# Connectors.net
KiCad netlist of a schematic drawn in Altium Designer
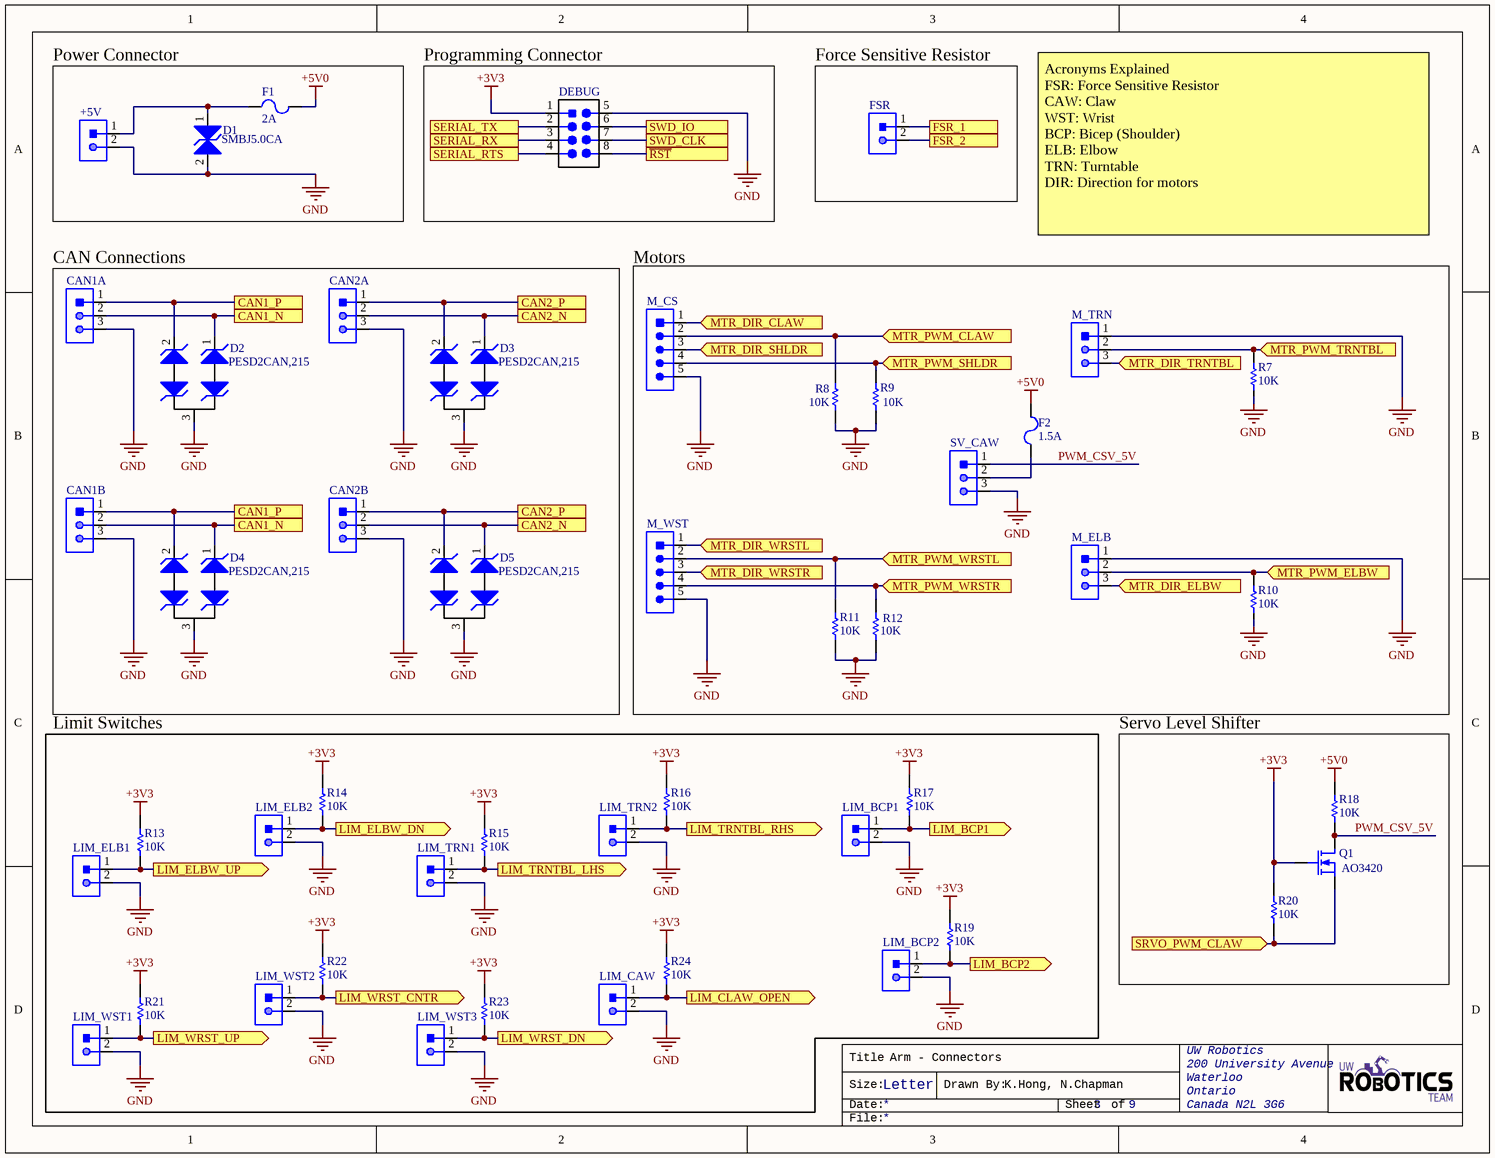
[diagram p0: Connectors.SchDoc]

(export (version "E")
  (design (tool "Eeschema 10.0.6"))
  (components
    (comp (ref "+5V")
      (value "CON_2M_SM4")
      (footprint "JST-B2B-SM4-TB")
      (description "CONN HEADER SMD 2POS 2MM")
      (fields
        (field (name "MANUFACTURER") "JST")
        (field (name "MANUFACTURER PART NUMBER") "B2B-PH-SM4-TB(LF)(SN)")
      )
      (libsource (lib "UWRT_Schematic_Library_2020") (part "CON_2M_SM4"))
    )
    (comp (ref "CAN1A")
      (value "CON_3M_SM4")
      (footprint "JST-B3B-SM4-TB")
      (description "CONN HEADER SMD 3POS 2MM")
      (fields
        (field (name "MANUFACTURER") "JST")
        (field (name "MANUFACTURER PART NUMBER") "B3B-PH-SM4-TB(LF)(SN)")
      )
      (libsource (lib "UWRT_Schematic_Library_2020") (part "CON_3M_SM4"))
    )
    (comp (ref "CAN1B")
      (value "CON_3M_SM4")
      (footprint "JST-B3B-SM4-TB")
      (description "CONN HEADER SMD 3POS 2MM")
      (fields
        (field (name "MANUFACTURER") "JST")
        (field (name "MANUFACTURER PART NUMBER") "B3B-PH-SM4-TB(LF)(SN)")
      )
      (libsource (lib "UWRT_Schematic_Library_2020") (part "CON_3M_SM4"))
    )
    (comp (ref "CAN2A")
      (value "CON_3M_SM4")
      (footprint "JST-B3B-SM4-TB")
      (description "CONN HEADER SMD 3POS 2MM")
      (fields
        (field (name "MANUFACTURER") "JST")
        (field (name "MANUFACTURER PART NUMBER") "B3B-PH-SM4-TB(LF)(SN)")
      )
      (libsource (lib "UWRT_Schematic_Library_2020") (part "CON_3M_SM4"))
    )
    (comp (ref "CAN2B")
      (value "CON_3M_SM4")
      (footprint "JST-B3B-SM4-TB")
      (description "CONN HEADER SMD 3POS 2MM")
      (fields
        (field (name "MANUFACTURER") "JST")
        (field (name "MANUFACTURER PART NUMBER") "B3B-PH-SM4-TB(LF)(SN)")
      )
      (libsource (lib "UWRT_Schematic_Library_2020") (part "CON_3M_SM4"))
    )
    (comp (ref "D1")
      (value "TVS_DIODE_BIDIRECTIONAL")
      (footprint "TVS_DIODE_BIDIRECTIONAL")
      (description "TVS DIODE 5V 9.2V DO214AA")
      (fields (field (name "MANUFACTURER PART NUMBER 1") "SMBJ5.0CA"))
      (libsource (lib "UWRT_Schematic_Library_2020") (part "TVS_DIODE_BIDIRECTIONAL"))
    )
    (comp (ref "D2")
      (value "TVS_DIODE_CAN")
      (footprint "NXP-SOT323-3")
      (description "TVS DIODE 24V 41V SOT323-3")
      (fields
        (field (name "MANUFACTURER") "Nexperia USA Inc.")
        (field (name "MANUFACTURER PART NUMBER") "PESD2CAN,215")
      )
      (libsource (lib "UWRT_Schematic_Library_2020") (part "TVS_DIODE_CAN"))
    )
    (comp (ref "D3")
      (value "TVS_DIODE_CAN")
      (footprint "NXP-SOT323-3")
      (description "TVS DIODE 24V 41V SOT323-3")
      (fields
        (field (name "MANUFACTURER") "Nexperia USA Inc.")
        (field (name "MANUFACTURER PART NUMBER") "PESD2CAN,215")
      )
      (libsource (lib "UWRT_Schematic_Library_2020") (part "TVS_DIODE_CAN"))
    )
    (comp (ref "D4")
      (value "TVS_DIODE_CAN")
      (footprint "NXP-SOT323-3")
      (description "TVS DIODE 24V 41V SOT323-3")
      (fields
        (field (name "MANUFACTURER") "Nexperia USA Inc.")
        (field (name "MANUFACTURER PART NUMBER") "PESD2CAN,215")
      )
      (libsource (lib "UWRT_Schematic_Library_2020") (part "TVS_DIODE_CAN"))
    )
    (comp (ref "D5")
      (value "TVS_DIODE_CAN")
      (footprint "NXP-SOT323-3")
      (description "TVS DIODE 24V 41V SOT323-3")
      (fields
        (field (name "MANUFACTURER") "Nexperia USA Inc.")
        (field (name "MANUFACTURER PART NUMBER") "PESD2CAN,215")
      )
      (libsource (lib "UWRT_Schematic_Library_2020") (part "TVS_DIODE_CAN"))
    )
    (comp (ref "DEBUG")
      (value "HEADER 4X2")
      (footprint "HEADER_2X4")
      (description "CONN HEADER VERT 8POS 2.54MM")
      (libsource (lib "UWRT_Schematic_Library_2020") (part "HEADER 4X2"))
    )
    (comp (ref "F1")
      (value "FUSE_2A_0603")
      (footprint "FUSE_0603")
      (description "FUSE SMD 2A 32V")
      (fields (field (name "CURRENT RATING") "2A"))
      (libsource (lib "UWRT_Schematic_Library_2020") (part "FUSE_2A_0603"))
    )
    (comp (ref "F2")
      (value "FUSE_1.5A_0603")
      (footprint "FUSE_0603")
      (description "FUSE SMD 1.5A 32V")
      (fields (field (name "CURRENT RATING") "1.5A"))
      (libsource (lib "UWRT_Schematic_Library_2020") (part "FUSE_1.5A_0603"))
    )
    (comp (ref "FSR")
      (value "CON_2M_SM4")
      (footprint "JST-B2B-SM4-TB")
      (description "CONN HEADER SMD 2POS 2MM")
      (fields
        (field (name "MANUFACTURER") "JST")
        (field (name "MANUFACTURER PART NUMBER") "B2B-PH-SM4-TB(LF)(SN)")
      )
      (libsource (lib "UWRT_Schematic_Library_2020") (part "CON_2M_SM4"))
    )
    (comp (ref "LIM_BCP1")
      (value "CON_2M_SM4")
      (footprint "JST-B2B-SM4-TB")
      (description "CONN HEADER SMD 2POS 2MM")
      (fields
        (field (name "MANUFACTURER") "JST")
        (field (name "MANUFACTURER PART NUMBER") "B2B-PH-SM4-TB(LF)(SN)")
      )
      (libsource (lib "UWRT_Schematic_Library_2020") (part "CON_2M_SM4"))
    )
    (comp (ref "LIM_BCP2")
      (value "CON_2M_SM4")
      (footprint "JST-B2B-SM4-TB")
      (description "CONN HEADER SMD 2POS 2MM")
      (fields
        (field (name "MANUFACTURER") "JST")
        (field (name "MANUFACTURER PART NUMBER") "B2B-PH-SM4-TB(LF)(SN)")
      )
      (libsource (lib "UWRT_Schematic_Library_2020") (part "CON_2M_SM4"))
    )
    (comp (ref "LIM_CAW")
      (value "CON_2M_SM4")
      (footprint "JST-B2B-SM4-TB")
      (description "CONN HEADER SMD 2POS 2MM")
      (fields
        (field (name "MANUFACTURER") "JST")
        (field (name "MANUFACTURER PART NUMBER") "B2B-PH-SM4-TB(LF)(SN)")
      )
      (libsource (lib "UWRT_Schematic_Library_2020") (part "CON_2M_SM4"))
    )
    (comp (ref "LIM_ELB1")
      (value "CON_2M_SM4")
      (footprint "JST-B2B-SM4-TB")
      (description "CONN HEADER SMD 2POS 2MM")
      (fields
        (field (name "MANUFACTURER") "JST")
        (field (name "MANUFACTURER PART NUMBER") "B2B-PH-SM4-TB(LF)(SN)")
      )
      (libsource (lib "UWRT_Schematic_Library_2020") (part "CON_2M_SM4"))
    )
    (comp (ref "LIM_ELB2")
      (value "CON_2M_SM4")
      (footprint "JST-B2B-SM4-TB")
      (description "CONN HEADER SMD 2POS 2MM")
      (fields
        (field (name "MANUFACTURER") "JST")
        (field (name "MANUFACTURER PART NUMBER") "B2B-PH-SM4-TB(LF)(SN)")
      )
      (libsource (lib "UWRT_Schematic_Library_2020") (part "CON_2M_SM4"))
    )
    (comp (ref "LIM_TRN1")
      (value "CON_2M_SM4")
      (footprint "JST-B2B-SM4-TB")
      (description "CONN HEADER SMD 2POS 2MM")
      (fields
        (field (name "MANUFACTURER") "JST")
        (field (name "MANUFACTURER PART NUMBER") "B2B-PH-SM4-TB(LF)(SN)")
      )
      (libsource (lib "UWRT_Schematic_Library_2020") (part "CON_2M_SM4"))
    )
    (comp (ref "LIM_TRN2")
      (value "CON_2M_SM4")
      (footprint "JST-B2B-SM4-TB")
      (description "CONN HEADER SMD 2POS 2MM")
      (fields
        (field (name "MANUFACTURER") "JST")
        (field (name "MANUFACTURER PART NUMBER") "B2B-PH-SM4-TB(LF)(SN)")
      )
      (libsource (lib "UWRT_Schematic_Library_2020") (part "CON_2M_SM4"))
    )
    (comp (ref "LIM_WST1")
      (value "CON_2M_SM4")
      (footprint "JST-B2B-SM4-TB")
      (description "CONN HEADER SMD 2POS 2MM")
      (fields
        (field (name "MANUFACTURER") "JST")
        (field (name "MANUFACTURER PART NUMBER") "B2B-PH-SM4-TB(LF)(SN)")
      )
      (libsource (lib "UWRT_Schematic_Library_2020") (part "CON_2M_SM4"))
    )
    (comp (ref "LIM_WST2")
      (value "CON_2M_SM4")
      (footprint "JST-B2B-SM4-TB")
      (description "CONN HEADER SMD 2POS 2MM")
      (fields
        (field (name "MANUFACTURER") "JST")
        (field (name "MANUFACTURER PART NUMBER") "B2B-PH-SM4-TB(LF)(SN)")
      )
      (libsource (lib "UWRT_Schematic_Library_2020") (part "CON_2M_SM4"))
    )
    (comp (ref "LIM_WST3")
      (value "CON_2M_SM4")
      (footprint "JST-B2B-SM4-TB")
      (description "CONN HEADER SMD 2POS 2MM")
      (fields
        (field (name "MANUFACTURER") "JST")
        (field (name "MANUFACTURER PART NUMBER") "B2B-PH-SM4-TB(LF)(SN)")
      )
      (libsource (lib "UWRT_Schematic_Library_2020") (part "CON_2M_SM4"))
    )
    (comp (ref "M_CS")
      (value "CON_5M_SM4")
      (footprint "JST-B5B-SM4-TB")
      (description "CONN HEADER SMD 5POS 2MM")
      (fields
        (field (name "MANUFACTURER") "JST")
        (field (name "MANUFACTURER PART NUMBER") "B5B-PH-SM4-TB(LF)(SN)")
      )
      (libsource (lib "UWRT_Schematic_Library_2020") (part "CON_5M_SM4"))
    )
    (comp (ref "M_ELB")
      (value "CON_3M_SM4")
      (footprint "JST-B3B-SM4-TB")
      (description "CONN HEADER SMD 3POS 2MM")
      (fields
        (field (name "MANUFACTURER") "JST")
        (field (name "MANUFACTURER PART NUMBER") "B3B-PH-SM4-TB(LF)(SN)")
      )
      (libsource (lib "UWRT_Schematic_Library_2020") (part "CON_3M_SM4"))
    )
    (comp (ref "M_TRN")
      (value "CON_3M_SM4")
      (footprint "JST-B3B-SM4-TB")
      (description "CONN HEADER SMD 3POS 2MM")
      (fields
        (field (name "MANUFACTURER") "JST")
        (field (name "MANUFACTURER PART NUMBER") "B3B-PH-SM4-TB(LF)(SN)")
      )
      (libsource (lib "UWRT_Schematic_Library_2020") (part "CON_3M_SM4"))
    )
    (comp (ref "M_WST")
      (value "CON_5M_SM4")
      (footprint "JST-B5B-SM4-TB")
      (description "CONN HEADER SMD 5POS 2MM")
      (fields
        (field (name "MANUFACTURER") "JST")
        (field (name "MANUFACTURER PART NUMBER") "B5B-PH-SM4-TB(LF)(SN)")
      )
      (libsource (lib "UWRT_Schematic_Library_2020") (part "CON_5M_SM4"))
    )
    (comp (ref "Q1")
      (value "NMOS_20V_6A")
      (footprint "NMOS_SOT23-3")
      (description "MOSFET N-CH 20V 6A SOT23")
      (fields (field (name "MPN") "AO3420") (field (name "MANUFACTURER") "Alpha & Omega"))
      (libsource (lib "UWRT_Schematic_Library_2020") (part "NMOS_20V_6A"))
    )
    (comp (ref "R7")
      (value "10K")
      (footprint "RESC0603(1608)_N")
      (description "RES SMD 10K OHM 5% 1/10W 0603")
      (fields (field (name "MANUFACTURER") "Yageo") (field (name "MPN") "RC0603JR-0710KL"))
      (libsource (lib "UWRT_Schematic_Library_2020") (part "RES_10K_0603"))
    )
    (comp (ref "R8")
      (value "10K")
      (footprint "RESC0603(1608)_N")
      (description "RES SMD 10K OHM 5% 1/10W 0603")
      (fields (field (name "MANUFACTURER") "Yageo") (field (name "MPN") "RC0603JR-0710KL"))
      (libsource (lib "UWRT_Schematic_Library_2020") (part "RES_10K_0603"))
    )
    (comp (ref "R9")
      (value "10K")
      (footprint "RESC0603(1608)_N")
      (description "RES SMD 10K OHM 5% 1/10W 0603")
      (fields (field (name "MANUFACTURER") "Yageo") (field (name "MPN") "RC0603JR-0710KL"))
      (libsource (lib "UWRT_Schematic_Library_2020") (part "RES_10K_0603"))
    )
    (comp (ref "R10")
      (value "10K")
      (footprint "RESC0603(1608)_N")
      (description "RES SMD 10K OHM 5% 1/10W 0603")
      (fields (field (name "MANUFACTURER") "Yageo") (field (name "MPN") "RC0603JR-0710KL"))
      (libsource (lib "UWRT_Schematic_Library_2020") (part "RES_10K_0603"))
    )
    (comp (ref "R11")
      (value "10K")
      (footprint "RESC0603(1608)_N")
      (description "RES SMD 10K OHM 5% 1/10W 0603")
      (fields (field (name "MANUFACTURER") "Yageo") (field (name "MPN") "RC0603JR-0710KL"))
      (libsource (lib "UWRT_Schematic_Library_2020") (part "RES_10K_0603"))
    )
    (comp (ref "R12")
      (value "10K")
      (footprint "RESC0603(1608)_N")
      (description "RES SMD 10K OHM 5% 1/10W 0603")
      (fields (field (name "MANUFACTURER") "Yageo") (field (name "MPN") "RC0603JR-0710KL"))
      (libsource (lib "UWRT_Schematic_Library_2020") (part "RES_10K_0603"))
    )
    (comp (ref "R13")
      (value "10K")
      (footprint "RESC0603(1608)_N")
      (description "RES SMD 10K OHM 5% 1/10W 0603")
      (fields (field (name "MANUFACTURER") "Yageo") (field (name "MPN") "RC0603JR-0710KL"))
      (libsource (lib "UWRT_Schematic_Library_2020") (part "RES_10K_0603"))
    )
    (comp (ref "R14")
      (value "10K")
      (footprint "RESC0603(1608)_N")
      (description "RES SMD 10K OHM 5% 1/10W 0603")
      (fields (field (name "MANUFACTURER") "Yageo") (field (name "MPN") "RC0603JR-0710KL"))
      (libsource (lib "UWRT_Schematic_Library_2020") (part "RES_10K_0603"))
    )
    (comp (ref "R15")
      (value "10K")
      (footprint "RESC0603(1608)_N")
      (description "RES SMD 10K OHM 5% 1/10W 0603")
      (fields (field (name "MANUFACTURER") "Yageo") (field (name "MPN") "RC0603JR-0710KL"))
      (libsource (lib "UWRT_Schematic_Library_2020") (part "RES_10K_0603"))
    )
    (comp (ref "R16")
      (value "10K")
      (footprint "RESC0603(1608)_N")
      (description "RES SMD 10K OHM 5% 1/10W 0603")
      (fields (field (name "MANUFACTURER") "Yageo") (field (name "MPN") "RC0603JR-0710KL"))
      (libsource (lib "UWRT_Schematic_Library_2020") (part "RES_10K_0603"))
    )
    (comp (ref "R17")
      (value "10K")
      (footprint "RESC0603(1608)_N")
      (description "RES SMD 10K OHM 5% 1/10W 0603")
      (fields (field (name "MANUFACTURER") "Yageo") (field (name "MPN") "RC0603JR-0710KL"))
      (libsource (lib "UWRT_Schematic_Library_2020") (part "RES_10K_0603"))
    )
    (comp (ref "R18")
      (value "10K")
      (footprint "RESC0603(1608)_N")
      (description "RES SMD 10K OHM 5% 1/10W 0603")
      (fields (field (name "MANUFACTURER") "Yageo") (field (name "MPN") "RC0603JR-0710KL"))
      (libsource (lib "UWRT_Schematic_Library_2020") (part "RES_10K_0603"))
    )
    (comp (ref "R19")
      (value "10K")
      (footprint "RESC0603(1608)_N")
      (description "RES SMD 10K OHM 5% 1/10W 0603")
      (fields (field (name "MANUFACTURER") "Yageo") (field (name "MPN") "RC0603JR-0710KL"))
      (libsource (lib "UWRT_Schematic_Library_2020") (part "RES_10K_0603"))
    )
    (comp (ref "R20")
      (value "10K")
      (footprint "RESC0603(1608)_N")
      (description "RES SMD 10K OHM 5% 1/10W 0603")
      (fields (field (name "MANUFACTURER") "Yageo") (field (name "MPN") "RC0603JR-0710KL"))
      (libsource (lib "UWRT_Schematic_Library_2020") (part "RES_10K_0603"))
    )
    (comp (ref "R21")
      (value "10K")
      (footprint "RESC0603(1608)_N")
      (description "RES SMD 10K OHM 5% 1/10W 0603")
      (fields (field (name "MANUFACTURER") "Yageo") (field (name "MPN") "RC0603JR-0710KL"))
      (libsource (lib "UWRT_Schematic_Library_2020") (part "RES_10K_0603"))
    )
    (comp (ref "R22")
      (value "10K")
      (footprint "RESC0603(1608)_N")
      (description "RES SMD 10K OHM 5% 1/10W 0603")
      (fields (field (name "MANUFACTURER") "Yageo") (field (name "MPN") "RC0603JR-0710KL"))
      (libsource (lib "UWRT_Schematic_Library_2020") (part "RES_10K_0603"))
    )
    (comp (ref "R23")
      (value "10K")
      (footprint "RESC0603(1608)_N")
      (description "RES SMD 10K OHM 5% 1/10W 0603")
      (fields (field (name "MANUFACTURER") "Yageo") (field (name "MPN") "RC0603JR-0710KL"))
      (libsource (lib "UWRT_Schematic_Library_2020") (part "RES_10K_0603"))
    )
    (comp (ref "R24")
      (value "10K")
      (footprint "RESC0603(1608)_N")
      (description "RES SMD 10K OHM 5% 1/10W 0603")
      (fields (field (name "MANUFACTURER") "Yageo") (field (name "MPN") "RC0603JR-0710KL"))
      (libsource (lib "UWRT_Schematic_Library_2020") (part "RES_10K_0603"))
    )
    (comp (ref "SV_CAW")
      (value "CON_3M_SM4")
      (footprint "JST-B3B-SM4-TB")
      (description "CONN HEADER SMD 3POS 2MM")
      (fields
        (field (name "MANUFACTURER") "JST")
        (field (name "MANUFACTURER PART NUMBER") "B3B-PH-SM4-TB(LF)(SN)")
      )
      (libsource (lib "UWRT_Schematic_Library_2020") (part "CON_3M_SM4"))
    )
  )
  (nets
    (net (code "1") (name "+3V3") (class "Default")
      (node (ref "DEBUG") (pin "1") (pinfunction "VCC_1") (pintype "passive"))
      (node (ref "Q1") (pin "1") (pinfunction "G_1") (pintype "passive"))
      (node (ref "R13") (pin "2") (pinfunction "2_2") (pintype "passive"))
      (node (ref "R14") (pin "2") (pinfunction "2_2") (pintype "passive"))
      (node (ref "R15") (pin "2") (pinfunction "2_2") (pintype "passive"))
      (node (ref "R16") (pin "2") (pinfunction "2_2") (pintype "passive"))
      (node (ref "R17") (pin "2") (pinfunction "2_2") (pintype "passive"))
      (node (ref "R19") (pin "2") (pinfunction "2_2") (pintype "passive"))
      (node (ref "R20") (pin "2") (pinfunction "2_2") (pintype "passive"))
      (node (ref "R21") (pin "2") (pinfunction "2_2") (pintype "passive"))
      (node (ref "R22") (pin "2") (pinfunction "2_2") (pintype "passive"))
      (node (ref "R23") (pin "2") (pinfunction "2_2") (pintype "passive"))
      (node (ref "R24") (pin "2") (pinfunction "2_2") (pintype "passive"))
    )
    (net (code "2") (name "+5V0") (class "Default")
      (node (ref "F1") (pin "2") (pinfunction "2_2") (pintype "passive"))
      (node (ref "F2") (pin "2") (pinfunction "2_2") (pintype "passive"))
      (node (ref "R18") (pin "2") (pinfunction "2_2") (pintype "passive"))
    )
    (net (code "3") (name "/CAN1_N") (class "Default")
      (node (ref "CAN1A") (pin "2") (pinfunction "2_2") (pintype "passive"))
      (node (ref "CAN1B") (pin "2") (pinfunction "2_2") (pintype "passive"))
      (node (ref "D2") (pin "1") (pinfunction "1_1") (pintype "passive"))
      (node (ref "D4") (pin "1") (pinfunction "1_1") (pintype "passive"))
    )
    (net (code "4") (name "/CAN1_P") (class "Default")
      (node (ref "CAN1A") (pin "1") (pinfunction "1_1") (pintype "passive"))
      (node (ref "CAN1B") (pin "1") (pinfunction "1_1") (pintype "passive"))
      (node (ref "D2") (pin "2") (pinfunction "2_2") (pintype "passive"))
      (node (ref "D4") (pin "2") (pinfunction "2_2") (pintype "passive"))
    )
    (net (code "5") (name "/CAN2_N") (class "Default")
      (node (ref "CAN2A") (pin "2") (pinfunction "2_2") (pintype "passive"))
      (node (ref "CAN2B") (pin "2") (pinfunction "2_2") (pintype "passive"))
      (node (ref "D3") (pin "1") (pinfunction "1_1") (pintype "passive"))
      (node (ref "D5") (pin "1") (pinfunction "1_1") (pintype "passive"))
    )
    (net (code "6") (name "/CAN2_P") (class "Default")
      (node (ref "CAN2A") (pin "1") (pinfunction "1_1") (pintype "passive"))
      (node (ref "CAN2B") (pin "1") (pinfunction "1_1") (pintype "passive"))
      (node (ref "D3") (pin "2") (pinfunction "2_2") (pintype "passive"))
      (node (ref "D5") (pin "2") (pinfunction "2_2") (pintype "passive"))
    )
    (net (code "7") (name "/FSR_1") (class "Default")
      (node (ref "FSR") (pin "1") (pinfunction "1_1") (pintype "passive"))
    )
    (net (code "8") (name "/FSR_2") (class "Default")
      (node (ref "FSR") (pin "2") (pinfunction "2_2") (pintype "passive"))
    )
    (net (code "9") (name "/LIM_BCP1") (class "Default")
      (node (ref "LIM_BCP1") (pin "1") (pinfunction "1_1") (pintype "passive"))
      (node (ref "R17") (pin "1") (pinfunction "1_1") (pintype "passive"))
    )
    (net (code "10") (name "/LIM_BCP2") (class "Default")
      (node (ref "LIM_BCP2") (pin "1") (pinfunction "1_1") (pintype "passive"))
      (node (ref "R19") (pin "1") (pinfunction "1_1") (pintype "passive"))
    )
    (net (code "11") (name "/LIM_CLAW_OPEN") (class "Default")
      (node (ref "LIM_CAW") (pin "1") (pinfunction "1_1") (pintype "passive"))
      (node (ref "R24") (pin "1") (pinfunction "1_1") (pintype "passive"))
    )
    (net (code "12") (name "/LIM_ELBW_DN") (class "Default")
      (node (ref "LIM_ELB2") (pin "1") (pinfunction "1_1") (pintype "passive"))
      (node (ref "R14") (pin "1") (pinfunction "1_1") (pintype "passive"))
    )
    (net (code "13") (name "/LIM_ELBW_UP") (class "Default")
      (node (ref "LIM_ELB1") (pin "1") (pinfunction "1_1") (pintype "passive"))
      (node (ref "R13") (pin "1") (pinfunction "1_1") (pintype "passive"))
    )
    (net (code "14") (name "/LIM_TRNTBL_LHS") (class "Default")
      (node (ref "LIM_TRN1") (pin "1") (pinfunction "1_1") (pintype "passive"))
      (node (ref "R15") (pin "1") (pinfunction "1_1") (pintype "passive"))
    )
    (net (code "15") (name "/LIM_TRNTBL_RHS") (class "Default")
      (node (ref "LIM_TRN2") (pin "1") (pinfunction "1_1") (pintype "passive"))
      (node (ref "R16") (pin "1") (pinfunction "1_1") (pintype "passive"))
    )
    (net (code "16") (name "/LIM_WRST_CNTR") (class "Default")
      (node (ref "LIM_WST2") (pin "1") (pinfunction "1_1") (pintype "passive"))
      (node (ref "R22") (pin "1") (pinfunction "1_1") (pintype "passive"))
    )
    (net (code "17") (name "/LIM_WRST_DN") (class "Default")
      (node (ref "LIM_WST3") (pin "1") (pinfunction "1_1") (pintype "passive"))
      (node (ref "R23") (pin "1") (pinfunction "1_1") (pintype "passive"))
    )
    (net (code "18") (name "/LIM_WRST_UP") (class "Default")
      (node (ref "LIM_WST1") (pin "1") (pinfunction "1_1") (pintype "passive"))
      (node (ref "R21") (pin "1") (pinfunction "1_1") (pintype "passive"))
    )
    (net (code "19") (name "/MTR_DIR_CLAW") (class "Default")
      (node (ref "M_CS") (pin "1") (pinfunction "1_1") (pintype "passive"))
    )
    (net (code "20") (name "/MTR_DIR_ELBW") (class "Default")
      (node (ref "M_ELB") (pin "3") (pinfunction "3_3") (pintype "passive"))
    )
    (net (code "21") (name "/MTR_DIR_SHLDR") (class "Default")
      (node (ref "M_CS") (pin "3") (pinfunction "3_3") (pintype "passive"))
    )
    (net (code "22") (name "/MTR_DIR_TRNTBL") (class "Default")
      (node (ref "M_TRN") (pin "3") (pinfunction "3_3") (pintype "passive"))
    )
    (net (code "23") (name "/MTR_DIR_WRSTL") (class "Default")
      (node (ref "M_WST") (pin "1") (pinfunction "1_1") (pintype "passive"))
    )
    (net (code "24") (name "/MTR_DIR_WRSTR") (class "Default")
      (node (ref "M_WST") (pin "3") (pinfunction "3_3") (pintype "passive"))
    )
    (net (code "25") (name "/MTR_PWM_CLAW") (class "Default")
      (node (ref "M_CS") (pin "2") (pinfunction "2_2") (pintype "passive"))
      (node (ref "R8") (pin "2") (pinfunction "2_2") (pintype "passive"))
    )
    (net (code "26") (name "/MTR_PWM_ELBW") (class "Default")
      (node (ref "M_ELB") (pin "2") (pinfunction "2_2") (pintype "passive"))
      (node (ref "R10") (pin "2") (pinfunction "2_2") (pintype "passive"))
    )
    (net (code "27") (name "/MTR_PWM_SHLDR") (class "Default")
      (node (ref "M_CS") (pin "4") (pinfunction "4_4") (pintype "passive"))
      (node (ref "R9") (pin "2") (pinfunction "2_2") (pintype "passive"))
    )
    (net (code "28") (name "/MTR_PWM_TRNTBL") (class "Default")
      (node (ref "M_TRN") (pin "2") (pinfunction "2_2") (pintype "passive"))
      (node (ref "R7") (pin "2") (pinfunction "2_2") (pintype "passive"))
    )
    (net (code "29") (name "/MTR_PWM_WRSTL") (class "Default")
      (node (ref "M_WST") (pin "2") (pinfunction "2_2") (pintype "passive"))
      (node (ref "R11") (pin "2") (pinfunction "2_2") (pintype "passive"))
    )
    (net (code "30") (name "/MTR_PWM_WRSTR") (class "Default")
      (node (ref "M_WST") (pin "4") (pinfunction "4_4") (pintype "passive"))
      (node (ref "R12") (pin "2") (pinfunction "2_2") (pintype "passive"))
    )
    (net (code "31") (name "/PWM_CSV_5V") (class "Default")
      (node (ref "Q1") (pin "3") (pinfunction "D_3") (pintype "passive"))
      (node (ref "R18") (pin "1") (pinfunction "1_1") (pintype "passive"))
      (node (ref "SV_CAW") (pin "1") (pinfunction "1_1") (pintype "passive"))
    )
    (net (code "32") (name "/SERIAL_RTS") (class "Default")
      (node (ref "DEBUG") (pin "4") (pinfunction "4_4") (pintype "passive"))
    )
    (net (code "33") (name "/SERIAL_RX") (class "Default")
      (node (ref "DEBUG") (pin "3") (pinfunction "3_3") (pintype "passive"))
    )
    (net (code "34") (name "/SERIAL_TX") (class "Default")
      (node (ref "DEBUG") (pin "2") (pinfunction "2_2") (pintype "passive"))
    )
    (net (code "35") (name "/SRVO_PWM_CLAW") (class "Default")
      (node (ref "Q1") (pin "2") (pinfunction "S_2") (pintype "passive"))
      (node (ref "R20") (pin "1") (pinfunction "1_1") (pintype "passive"))
    )
    (net (code "36") (name "/SWD_CLK") (class "Default")
      (node (ref "DEBUG") (pin "7") (pinfunction "3_7") (pintype "passive"))
    )
    (net (code "37") (name "/SWD_IO") (class "Default")
      (node (ref "DEBUG") (pin "6") (pinfunction "2_6") (pintype "passive"))
    )
    (net (code "38") (name "/~{RST}") (class "Default")
      (node (ref "DEBUG") (pin "8") (pinfunction "4_8") (pintype "passive"))
    )
    (net (code "39") (name "GND") (class "Default")
      (node (ref "+5V") (pin "2") (pinfunction "2_2") (pintype "passive"))
      (node (ref "CAN1A") (pin "3") (pinfunction "3_3") (pintype "passive"))
      (node (ref "CAN1B") (pin "3") (pinfunction "3_3") (pintype "passive"))
      (node (ref "CAN2A") (pin "3") (pinfunction "3_3") (pintype "passive"))
      (node (ref "CAN2B") (pin "3") (pinfunction "3_3") (pintype "passive"))
      (node (ref "D1") (pin "2") (pinfunction "2_2") (pintype "passive"))
      (node (ref "D2") (pin "3") (pinfunction "3_3") (pintype "passive"))
      (node (ref "D3") (pin "3") (pinfunction "3_3") (pintype "passive"))
      (node (ref "D4") (pin "3") (pinfunction "3_3") (pintype "passive"))
      (node (ref "D5") (pin "3") (pinfunction "3_3") (pintype "passive"))
      (node (ref "DEBUG") (pin "5") (pinfunction "GND_5") (pintype "passive"))
      (node (ref "LIM_BCP1") (pin "2") (pinfunction "2_2") (pintype "passive"))
      (node (ref "LIM_BCP2") (pin "2") (pinfunction "2_2") (pintype "passive"))
      (node (ref "LIM_CAW") (pin "2") (pinfunction "2_2") (pintype "passive"))
      (node (ref "LIM_ELB1") (pin "2") (pinfunction "2_2") (pintype "passive"))
      (node (ref "LIM_ELB2") (pin "2") (pinfunction "2_2") (pintype "passive"))
      (node (ref "LIM_TRN1") (pin "2") (pinfunction "2_2") (pintype "passive"))
      (node (ref "LIM_TRN2") (pin "2") (pinfunction "2_2") (pintype "passive"))
      (node (ref "LIM_WST1") (pin "2") (pinfunction "2_2") (pintype "passive"))
      (node (ref "LIM_WST2") (pin "2") (pinfunction "2_2") (pintype "passive"))
      (node (ref "LIM_WST3") (pin "2") (pinfunction "2_2") (pintype "passive"))
      (node (ref "M_CS") (pin "5") (pinfunction "5_5") (pintype "passive"))
      (node (ref "M_ELB") (pin "1") (pinfunction "1_1") (pintype "passive"))
      (node (ref "M_TRN") (pin "1") (pinfunction "1_1") (pintype "passive"))
      (node (ref "M_WST") (pin "5") (pinfunction "5_5") (pintype "passive"))
      (node (ref "R10") (pin "1") (pinfunction "1_1") (pintype "passive"))
      (node (ref "R11") (pin "1") (pinfunction "1_1") (pintype "passive"))
      (node (ref "R12") (pin "1") (pinfunction "1_1") (pintype "passive"))
      (node (ref "R7") (pin "1") (pinfunction "1_1") (pintype "passive"))
      (node (ref "R8") (pin "1") (pinfunction "1_1") (pintype "passive"))
      (node (ref "R9") (pin "1") (pinfunction "1_1") (pintype "passive"))
      (node (ref "SV_CAW") (pin "3") (pinfunction "3_3") (pintype "passive"))
    )
    (net (code "40") (name "Net-(+5V-Pad1)") (class "Default")
      (node (ref "+5V") (pin "1") (pinfunction "1_1") (pintype "passive"))
      (node (ref "D1") (pin "1") (pinfunction "1_1") (pintype "passive"))
      (node (ref "F1") (pin "1") (pinfunction "1_1") (pintype "passive"))
    )
    (net (code "41") (name "Net-(F2-Pad1)") (class "Default")
      (node (ref "F2") (pin "1") (pinfunction "1_1") (pintype "passive"))
      (node (ref "SV_CAW") (pin "2") (pinfunction "2_2") (pintype "passive"))
    )
  )
)
